# design.net
KiCad netlist of a schematic drawn in EasyEDA Pro
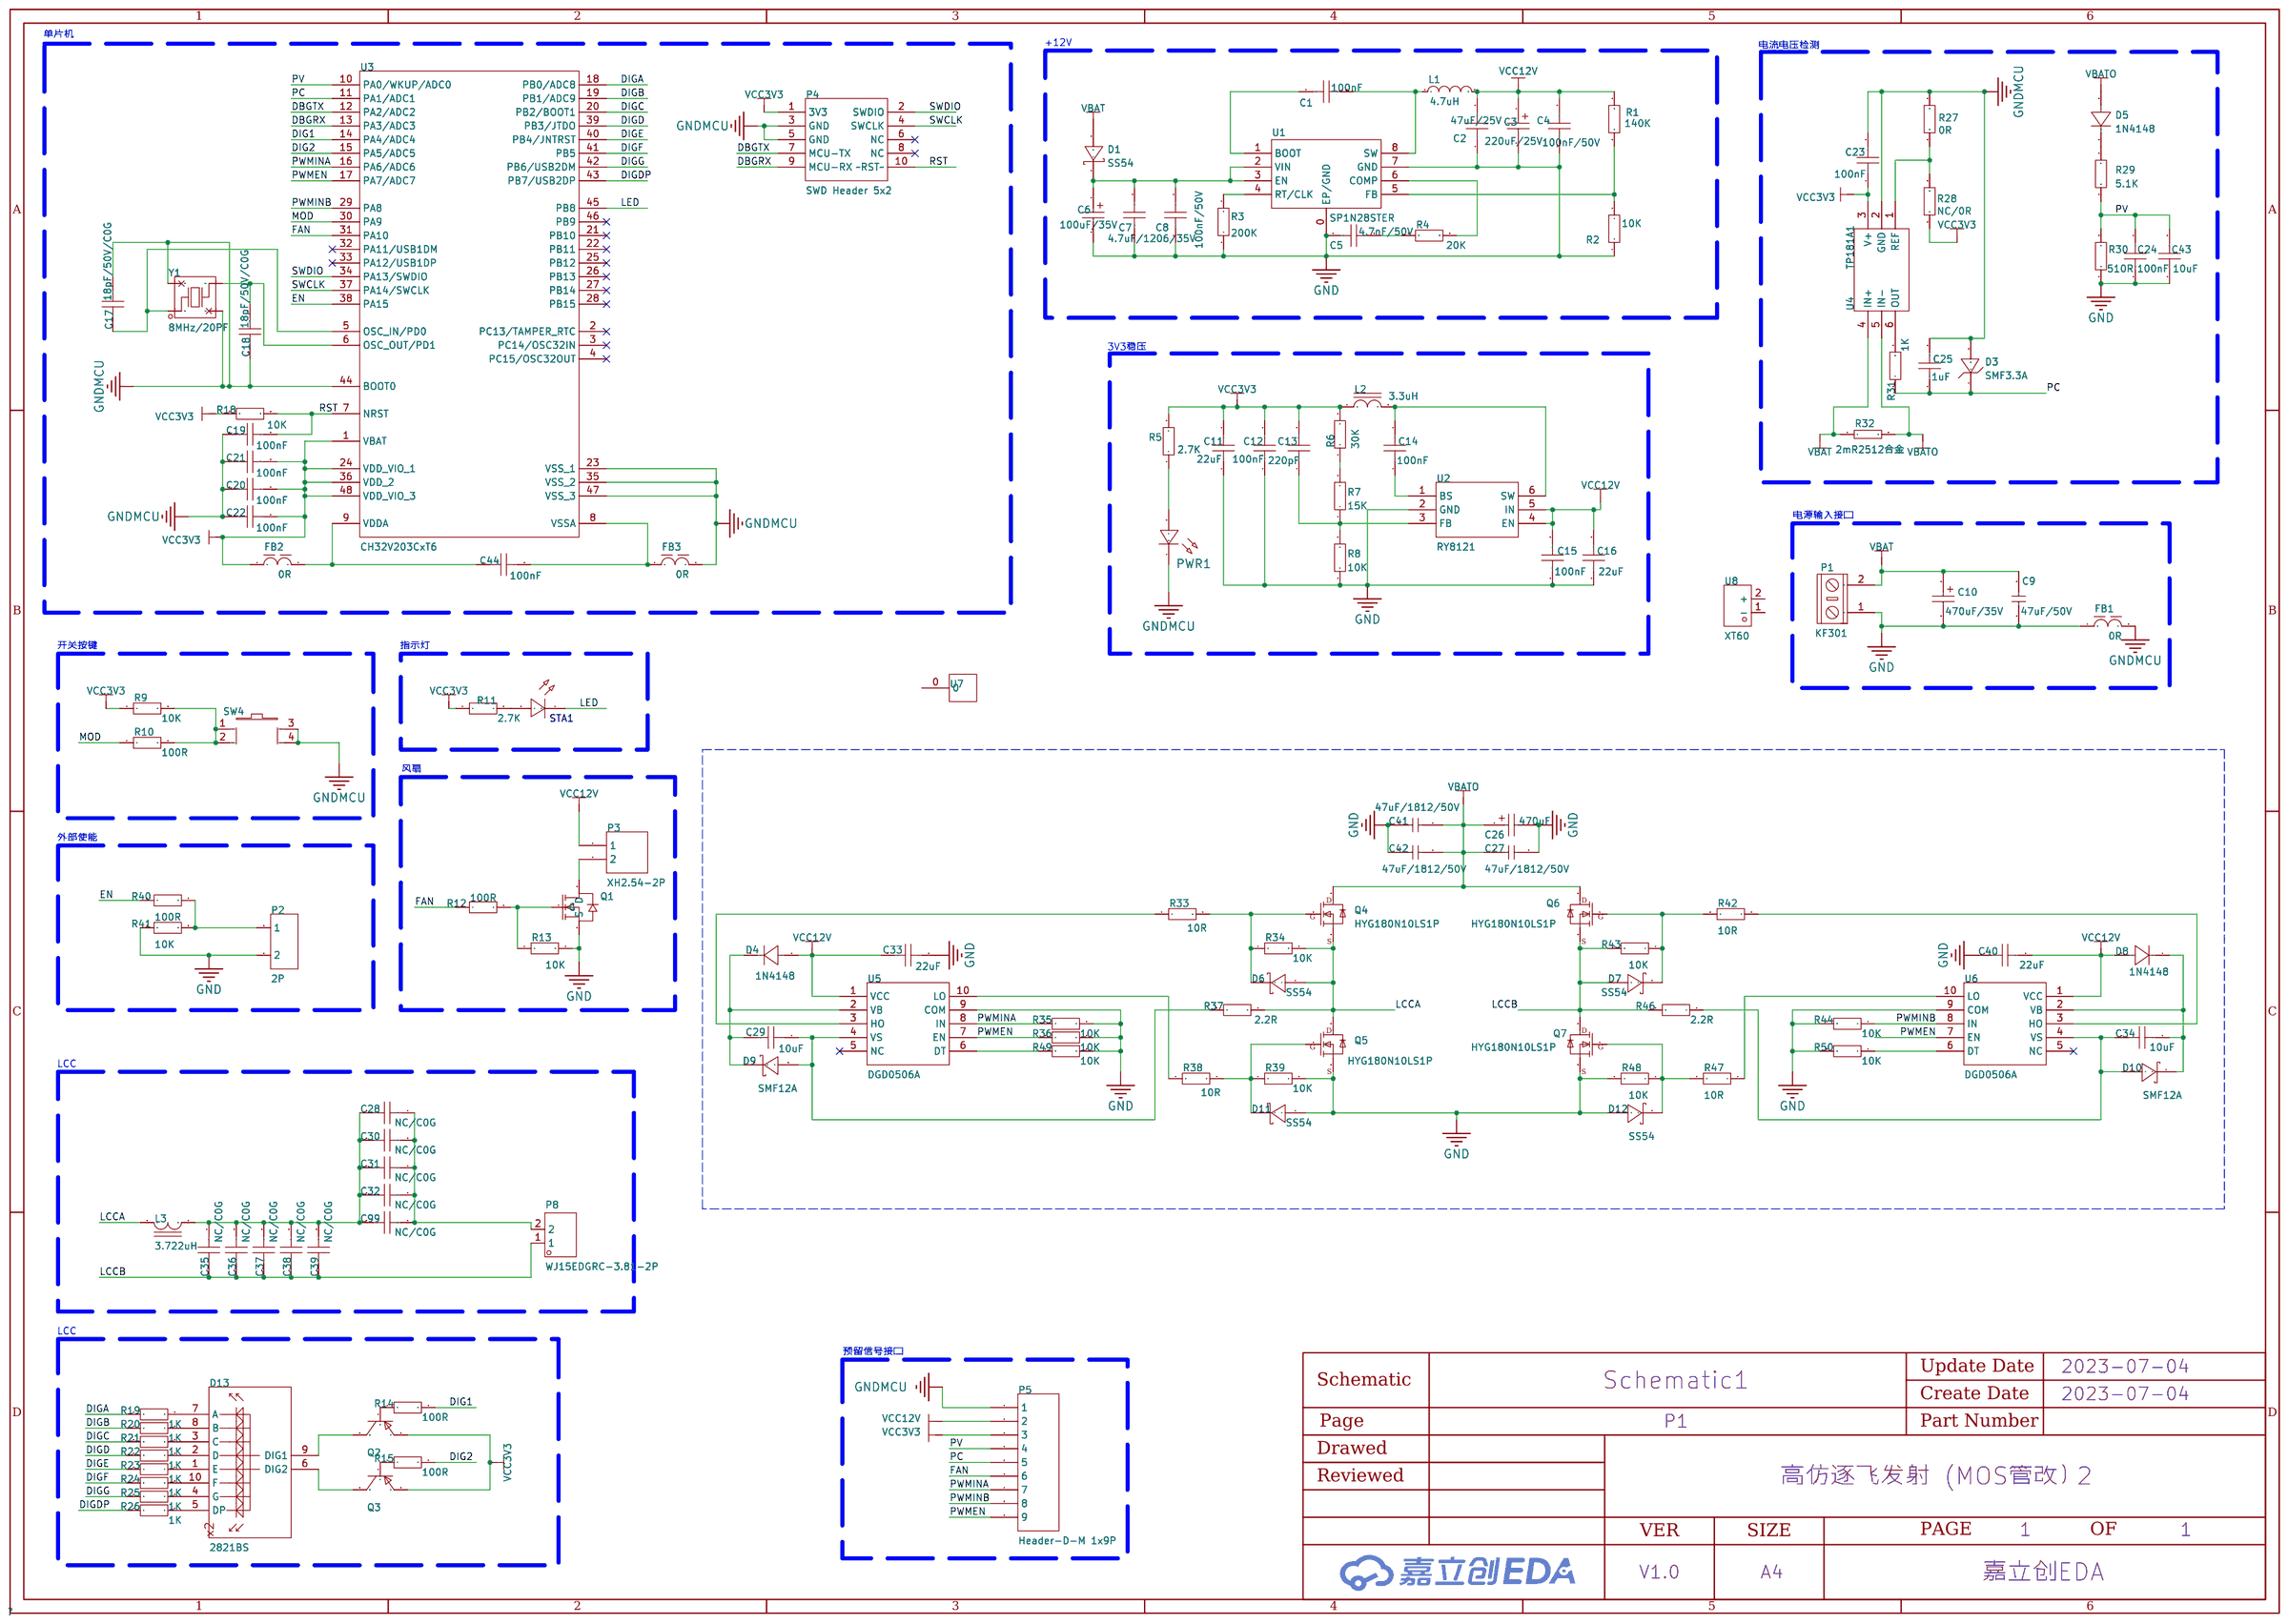
[diagram p0: schematic sheet]

(export (version "E")
  (design (tool "Eeschema 10.0.6"))
  (components
    (comp (ref "C1")
      (value "100nF")
      (footprint "easyedapro:C1206")
      (libsource (lib "easyedapro") (part "CapAcitance"))
    )
    (comp (ref "C2")
      (value "47uF/25V")
      (footprint "easyedapro:C1206")
      (libsource (lib "easyedapro") (part "CapAcitance"))
    )
    (comp (ref "C3")
      (value "220uF/25V")
      (footprint "easyedapro:Cap-S-D 2.5-6.3X8")
      (libsource (lib "easyedapro") (part "S-D 220uF 25V 6.3x8"))
    )
    (comp (ref "C4")
      (value "100nF/50V")
      (footprint "easyedapro:C1206")
      (libsource (lib "easyedapro") (part "CapAcitance"))
    )
    (comp (ref "C5")
      (value "4.7nF/50V")
      (footprint "easyedapro:C1206")
      (libsource (lib "easyedapro") (part "CapAcitance"))
    )
    (comp (ref "C6")
      (value "100uF/35V")
      (footprint "easyedapro:Cap-S-D 2.5-6.3X8")
      (libsource (lib "easyedapro") (part "S-D 100uF 35V 6.3x8"))
    )
    (comp (ref "C7")
      (value "4.7uF/1206/35V")
      (footprint "easyedapro:C1206")
      (libsource (lib "easyedapro") (part "CapAcitance"))
    )
    (comp (ref "C8")
      (value "100nF/50V")
      (footprint "easyedapro:C1206")
      (libsource (lib "easyedapro") (part "CapAcitance"))
    )
    (comp (ref "C9")
      (value "47uF/50V")
      (footprint "easyedapro:CAPC4532[1812]S")
      (libsource (lib "easyedapro") (part "47uF 1812 50V X5R"))
    )
    (comp (ref "C10")
      (value "470uF/35V")
      (footprint "easyedapro:Cap-S-D 3.5-8x14")
      (libsource (lib "easyedapro") (part "S-D 470uF 35V 8x14"))
    )
    (comp (ref "C11")
      (value "22uF")
      (footprint "easyedapro:C0805")
      (libsource (lib "easyedapro") (part "CapAcitance"))
    )
    (comp (ref "C12")
      (value "100nF")
      (footprint "easyedapro:C0805")
      (libsource (lib "easyedapro") (part "CapAcitance"))
    )
    (comp (ref "C13")
      (value "220pF")
      (footprint "easyedapro:C0805")
      (libsource (lib "easyedapro") (part "CapAcitance"))
    )
    (comp (ref "C14")
      (value "100nF")
      (footprint "easyedapro:C0805")
      (libsource (lib "easyedapro") (part "CapAcitance"))
    )
    (comp (ref "C15")
      (value "100nF")
      (footprint "easyedapro:C0805")
      (libsource (lib "easyedapro") (part "CapAcitance"))
    )
    (comp (ref "C16")
      (value "22uF")
      (footprint "easyedapro:C0805")
      (libsource (lib "easyedapro") (part "CapAcitance"))
    )
    (comp (ref "C17")
      (value "18pF/50V/C0G")
      (footprint "easyedapro:C0805")
      (libsource (lib "easyedapro") (part "CapAcitance"))
    )
    (comp (ref "C18")
      (value "18pF/50V/C0G")
      (footprint "easyedapro:C0805")
      (libsource (lib "easyedapro") (part "CapAcitance"))
    )
    (comp (ref "C19")
      (value "100nF")
      (footprint "easyedapro:C0805")
      (libsource (lib "easyedapro") (part "CapAcitance"))
    )
    (comp (ref "C20")
      (value "100nF")
      (footprint "easyedapro:C0805")
      (libsource (lib "easyedapro") (part "CapAcitance"))
    )
    (comp (ref "C21")
      (value "100nF")
      (footprint "easyedapro:C0805")
      (libsource (lib "easyedapro") (part "CapAcitance"))
    )
    (comp (ref "C22")
      (value "100nF")
      (footprint "easyedapro:C0805")
      (libsource (lib "easyedapro") (part "CapAcitance"))
    )
    (comp (ref "C23")
      (value "100nF")
      (footprint "easyedapro:C0805")
      (libsource (lib "easyedapro") (part "CapAcitance"))
    )
    (comp (ref "C24")
      (value "100nF")
      (footprint "easyedapro:C0805")
      (libsource (lib "easyedapro") (part "CapAcitance"))
    )
    (comp (ref "C25")
      (value "1uF")
      (footprint "easyedapro:C0805")
      (libsource (lib "easyedapro") (part "CapAcitance"))
    )
    (comp (ref "C26")
      (value "470uF")
      (footprint "easyedapro:Cap-S-D 3.5-8x14")
      (libsource (lib "easyedapro") (part "S-D 470uF 35V 8x14"))
    )
    (comp (ref "C27")
      (value "47uF/1812/50V")
      (footprint "easyedapro:CAPC4532[1812]S")
      (libsource (lib "easyedapro") (part "47uF 1812 50V X5R"))
    )
    (comp (ref "C28")
      (value "NC/C0G")
      (footprint "easyedapro:C0805")
      (libsource (lib "easyedapro") (part "CapAcitance"))
    )
    (comp (ref "C29")
      (value "10uF")
      (footprint "easyedapro:C0805")
      (libsource (lib "easyedapro") (part "CapAcitance"))
    )
    (comp (ref "C30")
      (value "NC/C0G")
      (footprint "easyedapro:C0805")
      (libsource (lib "easyedapro") (part "CapAcitance"))
    )
    (comp (ref "C31")
      (value "NC/C0G")
      (footprint "easyedapro:C0805")
      (libsource (lib "easyedapro") (part "CapAcitance"))
    )
    (comp (ref "C32")
      (value "NC/C0G")
      (footprint "easyedapro:C0805")
      (libsource (lib "easyedapro") (part "CapAcitance"))
    )
    (comp (ref "C33")
      (value "22uF")
      (footprint "easyedapro:C0805")
      (libsource (lib "easyedapro") (part "CapAcitance"))
    )
    (comp (ref "C34")
      (value "10uF")
      (footprint "easyedapro:C0805")
      (libsource (lib "easyedapro") (part "CapAcitance"))
    )
    (comp (ref "C35")
      (value "NC/C0G")
      (footprint "easyedapro:C0805")
      (libsource (lib "easyedapro") (part "CapAcitance"))
    )
    (comp (ref "C36")
      (value "NC/C0G")
      (footprint "easyedapro:C0805")
      (libsource (lib "easyedapro") (part "CapAcitance"))
    )
    (comp (ref "C37")
      (value "NC/C0G")
      (footprint "easyedapro:C0805")
      (libsource (lib "easyedapro") (part "CapAcitance"))
    )
    (comp (ref "C38")
      (value "NC/C0G")
      (footprint "easyedapro:C0805")
      (libsource (lib "easyedapro") (part "CapAcitance"))
    )
    (comp (ref "C39")
      (value "NC/C0G")
      (footprint "easyedapro:C0805")
      (libsource (lib "easyedapro") (part "CapAcitance"))
    )
    (comp (ref "C40")
      (value "22uF")
      (footprint "easyedapro:C0805")
      (libsource (lib "easyedapro") (part "CapAcitance"))
    )
    (comp (ref "C41")
      (value "47uF/1812/50V")
      (footprint "easyedapro:CAPC4532[1812]S")
      (libsource (lib "easyedapro") (part "47uF 1812 50V X5R"))
    )
    (comp (ref "C42")
      (value "47uF/1812/50V")
      (footprint "easyedapro:CAPC4532[1812]S")
      (libsource (lib "easyedapro") (part "47uF 1812 50V X5R"))
    )
    (comp (ref "C43")
      (value "10uF")
      (footprint "easyedapro:C0805")
      (libsource (lib "easyedapro") (part "CapAcitance"))
    )
    (comp (ref "C44")
      (value "100nF")
      (footprint "easyedapro:C0805")
      (libsource (lib "easyedapro") (part "CapAcitance"))
    )
    (comp (ref "C99")
      (value "NC/C0G")
      (footprint "easyedapro:C0805")
      (libsource (lib "easyedapro") (part "CapAcitance"))
    )
    (comp (ref "D1")
      (value "SS54")
      (footprint "easyedapro:SMA_L4.4-W2.8-LS5.4-R-RD")
      (description "直流反向耐压(Vr):40V;平均整流电流(Io):5A;正向压降(Vf):550mV@5A;")
      (fields (field (name "Manufacturer") "MDD"))
      (libsource (lib "easyedapro") (part "SS54_C22452"))
    )
    (comp (ref "D3")
      (value "SMF3.3A")
      (footprint "easyedapro:SOD-123_L2.8-W1.8-LS3.7-RD")
      (description "极性:单向;反向截止电压(Vrwm):3.3V;击穿电压:5.2V;反向漏电流(Ir):600uA;峰值脉冲电流(Ipp)@10/1000μs:25A;最大钳位电压:8V;")
      (fields (field (name "Manufacturer") "DOWO(东沃)"))
      (libsource (lib "easyedapro") (part "SMF3.3A"))
    )
    (comp (ref "D4")
      (value "1N4148")
      (footprint "easyedapro:SOD-123_L2.7-W1.6-LS3.7-RD")
      (fields (field (name "Manufacturer") "FUXINSEMI(富芯森美)"))
      (libsource (lib "easyedapro") (part "1N4148W_C908248"))
    )
    (comp (ref "D5")
      (value "1N4148")
      (footprint "easyedapro:SOD-123_L2.7-W1.6-LS3.7-RD")
      (fields (field (name "Manufacturer") "FUXINSEMI(富芯森美)"))
      (libsource (lib "easyedapro") (part "1N4148W_C908248"))
    )
    (comp (ref "D6")
      (value "SS54")
      (footprint "easyedapro:SMA_L4.4-W2.8-LS5.4-R-RD")
      (description "直流反向耐压(Vr):40V;平均整流电流(Io):5A;正向压降(Vf):550mV@5A;")
      (fields (field (name "Manufacturer") "MDD"))
      (libsource (lib "easyedapro") (part "SS54_C22452"))
    )
    (comp (ref "D7")
      (value "SS54")
      (footprint "easyedapro:SMA_L4.4-W2.8-LS5.4-R-RD")
      (description "直流反向耐压(Vr):40V;平均整流电流(Io):5A;正向压降(Vf):550mV@5A;")
      (fields (field (name "Manufacturer") "MDD"))
      (libsource (lib "easyedapro") (part "SS54_C22452"))
    )
    (comp (ref "D8")
      (value "1N4148")
      (footprint "easyedapro:SOD-123_L2.7-W1.6-LS3.7-RD")
      (fields (field (name "Manufacturer") "FUXINSEMI(富芯森美)"))
      (libsource (lib "easyedapro") (part "1N4148W_C908248"))
    )
    (comp (ref "D9")
      (value "SMF12A")
      (footprint "easyedapro:SOD-123F_L2.8-W1.8-LS3.7-RD")
      (description "极性:单向;反向截止电压(Vrwm):12V;击穿电压:13.3V;峰值脉冲电流(Ipp)@10/1000μs:-;最大钳位电压:19.9V;峰值脉冲功率(Ppp)@10/1000μs:200W;")
      (fields (field (name "Manufacturer") "Littelfuse(美国力特)"))
      (libsource (lib "easyedapro") (part "SMF12A_C207255"))
    )
    (comp (ref "D10")
      (value "SMF12A")
      (footprint "easyedapro:SOD-123F_L2.8-W1.8-LS3.7-RD")
      (description "极性:单向;反向截止电压(Vrwm):12V;击穿电压:13.3V;峰值脉冲电流(Ipp)@10/1000μs:-;最大钳位电压:19.9V;峰值脉冲功率(Ppp)@10/1000μs:200W;")
      (fields (field (name "Manufacturer") "Littelfuse(美国力特)"))
      (libsource (lib "easyedapro") (part "SMF12A_C207255"))
    )
    (comp (ref "D11")
      (value "SS54")
      (footprint "easyedapro:SMA_L4.4-W2.8-LS5.4-R-RD")
      (description "直流反向耐压(Vr):40V;平均整流电流(Io):5A;正向压降(Vf):550mV@5A;")
      (fields (field (name "Manufacturer") "MDD"))
      (libsource (lib "easyedapro") (part "SS54_C22452"))
    )
    (comp (ref "D12")
      (value "SS54")
      (footprint "easyedapro:SMA_L4.4-W2.8-LS5.4-R-RD")
      (description "直流反向耐压(Vr):40V;平均整流电流(Io):5A;正向压降(Vf):550mV@5A;")
      (fields (field (name "Manufacturer") "MDD"))
      (libsource (lib "easyedapro") (part "SS54_C22452"))
    )
    (comp (ref "D13")
      (value "2821BS")
      (footprint "easyedapro:2821AS/BS")
      (libsource (lib "easyedapro") (part "2821BS"))
    )
    (comp (ref "FB1")
      (value "0R")
      (footprint "easyedapro:INDC1608[0603]S")
      (libsource (lib "easyedapro") (part "FB-Chip"))
    )
    (comp (ref "FB2")
      (value "0R")
      (footprint "easyedapro:INDC1608[0603]S")
      (libsource (lib "easyedapro") (part "FB-Chip"))
    )
    (comp (ref "FB3")
      (value "0R")
      (footprint "easyedapro:INDC1608[0603]S")
      (libsource (lib "easyedapro") (part "FB-Chip"))
    )
    (comp (ref "L1")
      (value "4.7uH")
      (footprint "easyedapro:IND-SMD_L7.3-W6.6")
      (description "电感值:4.7uH;精度:±20%;额定电流:5.5A;饱和电流(Isat):7A;直流电阻(DCR):37mΩ;")
      (fields (field (name "Manufacturer Part") "MCS0630-4R7MPY1") (field (name "Manufacturer") "PSA(信昌电陶)"))
      (libsource (lib "easyedapro") (part "MCS0630-4R7MPY1"))
    )
    (comp (ref "L2")
      (value "3.3uH")
      (footprint "easyedapro:0402 TPC 4*4*2")
      (libsource (lib "easyedapro") (part "Ind-Power_1"))
    )
    (comp (ref "L3")
      (value "3.722uH")
      (footprint "easyedapro:T94/106-LAY")
      (libsource (lib "easyedapro") (part "Ind-Power_2"))
    )
    (comp (ref "P1")
      (value "KF301")
      (footprint "easyedapro:KF/WJ/DG 301-2p-5.0mm")
      (libsource (lib "easyedapro") (part "KF/WJ/DG 30x"))
    )
    (comp (ref "P2")
      (value "2P")
      (footprint "easyedapro:HDR-TH_2P-P2.54-V-M-1")
      (fields (field (name "Manufacturer") "TEConnectivity(美国泰科)"))
      (libsource (lib "easyedapro") (part "Header-Male-2.54_1x2"))
    )
    (comp (ref "P3")
      (value "XH2.54-2P")
      (footprint "easyedapro:XH2.54-2P-DV")
      (libsource (lib "easyedapro") (part "XH2.54-2P"))
    )
    (comp (ref "P4")
      (value "SWD Header 5x2")
      (footprint "easyedapro:HDR2X5-M")
      (libsource (lib "easyedapro") (part "SWD Header 5x2"))
    )
    (comp (ref "P5")
      (value "Header-D-M1x9P")
      (footprint "easyedapro:HDR1X9-M")
      (libsource (lib "easyedapro") (part "Header-D-M 1x9P"))
    )
    (comp (ref "P8")
      (value "WJ15EDGRC-3.81-2P")
      (footprint "easyedapro:CONN-TH_2P-P3.81_WJ15EDGRC-3.81-2P")
      (description "连接器类型:板端/插座-闭口;间距:3.81mm;排数:1;每排PIN数:2;安装方式:弯针;颜色:绿色;")
      (fields (field (name "Manufacturer") "KANGNEX(康奈克斯电气)"))
      (libsource (lib "easyedapro") (part "WJ15EDGRC-3.81-2P"))
    )
    (comp (ref "PWR1")
      (value "~")
      (footprint "easyedapro:LED_0603")
      (libsource (lib "easyedapro") (part "LED_R"))
    )
    (comp (ref "Q1")
      (value "~")
      (footprint "easyedapro:SOT-23-3_L2.9-W1.3-P1.90-LS2.4-BR")
      (libsource (lib "easyedapro") (part "N_MOS"))
    )
    (comp (ref "Q2")
      (value "~")
      (footprint "easyedapro:S8550P_SOT")
      (libsource (lib "easyedapro") (part "PNP"))
    )
    (comp (ref "Q3")
      (value "~")
      (footprint "easyedapro:S8550P_SOT")
      (libsource (lib "easyedapro") (part "PNP"))
    )
    (comp (ref "Q4")
      (value "HYG180N10LS1P")
      (footprint "easyedapro:TO-220-LAY")
      (libsource (lib "easyedapro") (part "HYG180N10LS1P"))
    )
    (comp (ref "Q5")
      (value "HYG180N10LS1P")
      (footprint "easyedapro:TO-220-LAY")
      (libsource (lib "easyedapro") (part "HYG180N10LS1P"))
    )
    (comp (ref "Q6")
      (value "HYG180N10LS1P")
      (footprint "easyedapro:TO-220-LAY")
      (libsource (lib "easyedapro") (part "HYG180N10LS1P"))
    )
    (comp (ref "Q7")
      (value "HYG180N10LS1P")
      (footprint "easyedapro:TO-220-LAY")
      (libsource (lib "easyedapro") (part "HYG180N10LS1P"))
    )
    (comp (ref "R1") (value "140K") (footprint "easyedapro:R0603") (libsource (lib "easyedapro") (part "电阻")))
    (comp (ref "R2") (value "10K") (footprint "easyedapro:R0603") (libsource (lib "easyedapro") (part "电阻")))
    (comp (ref "R3") (value "200K") (footprint "easyedapro:R0603") (libsource (lib "easyedapro") (part "电阻")))
    (comp (ref "R4") (value "20K") (footprint "easyedapro:R0603") (libsource (lib "easyedapro") (part "电阻")))
    (comp (ref "R5") (value "2.7K") (footprint "easyedapro:R0603") (libsource (lib "easyedapro") (part "电阻")))
    (comp (ref "R6") (value "30K") (footprint "easyedapro:R0603") (libsource (lib "easyedapro") (part "电阻")))
    (comp (ref "R7") (value "15K") (footprint "easyedapro:R0603") (libsource (lib "easyedapro") (part "电阻")))
    (comp (ref "R8") (value "10K") (footprint "easyedapro:R0603") (libsource (lib "easyedapro") (part "电阻")))
    (comp (ref "R9") (value "10K") (footprint "easyedapro:R0603") (libsource (lib "easyedapro") (part "电阻")))
    (comp (ref "R10")
      (value "100R")
      (footprint "easyedapro:R0603")
      (libsource (lib "easyedapro") (part "电阻"))
    )
    (comp (ref "R11")
      (value "2.7K")
      (footprint "easyedapro:R0603")
      (libsource (lib "easyedapro") (part "电阻"))
    )
    (comp (ref "R12")
      (value "100R")
      (footprint "easyedapro:R0603")
      (libsource (lib "easyedapro") (part "电阻"))
    )
    (comp (ref "R13") (value "10K") (footprint "easyedapro:R0603") (libsource (lib "easyedapro") (part "电阻")))
    (comp (ref "R14")
      (value "100R")
      (footprint "easyedapro:R0603")
      (libsource (lib "easyedapro") (part "电阻"))
    )
    (comp (ref "R15")
      (value "100R")
      (footprint "easyedapro:R0603")
      (libsource (lib "easyedapro") (part "电阻"))
    )
    (comp (ref "R18") (value "10K") (footprint "easyedapro:R0603") (libsource (lib "easyedapro") (part "电阻")))
    (comp (ref "R19") (value "1K") (footprint "easyedapro:R0603") (libsource (lib "easyedapro") (part "电阻")))
    (comp (ref "R20") (value "1K") (footprint "easyedapro:R0603") (libsource (lib "easyedapro") (part "电阻")))
    (comp (ref "R21") (value "1K") (footprint "easyedapro:R0603") (libsource (lib "easyedapro") (part "电阻")))
    (comp (ref "R22") (value "1K") (footprint "easyedapro:R0603") (libsource (lib "easyedapro") (part "电阻")))
    (comp (ref "R23") (value "1K") (footprint "easyedapro:R0603") (libsource (lib "easyedapro") (part "电阻")))
    (comp (ref "R24") (value "1K") (footprint "easyedapro:R0603") (libsource (lib "easyedapro") (part "电阻")))
    (comp (ref "R25") (value "1K") (footprint "easyedapro:R0603") (libsource (lib "easyedapro") (part "电阻")))
    (comp (ref "R26") (value "1K") (footprint "easyedapro:R0603") (libsource (lib "easyedapro") (part "电阻")))
    (comp (ref "R27") (value "0R") (footprint "easyedapro:R0603") (libsource (lib "easyedapro") (part "电阻")))
    (comp (ref "R28")
      (value "NC/0R")
      (footprint "easyedapro:R0603")
      (libsource (lib "easyedapro") (part "电阻"))
    )
    (comp (ref "R29")
      (value "5.1K")
      (footprint "easyedapro:R0603")
      (libsource (lib "easyedapro") (part "电阻"))
    )
    (comp (ref "R30")
      (value "510R")
      (footprint "easyedapro:R0603")
      (libsource (lib "easyedapro") (part "电阻"))
    )
    (comp (ref "R31") (value "1K") (footprint "easyedapro:R0603") (libsource (lib "easyedapro") (part "电阻")))
    (comp (ref "R32")
      (value "2mR2512合金")
      (footprint "easyedapro:RESC6332[2512]S")
      (libsource (lib "easyedapro") (part "Res-Chip_10"))
    )
    (comp (ref "R33") (value "10R") (footprint "easyedapro:R0603") (libsource (lib "easyedapro") (part "电阻")))
    (comp (ref "R34") (value "10K") (footprint "easyedapro:R0603") (libsource (lib "easyedapro") (part "电阻")))
    (comp (ref "R35") (value "10K") (footprint "easyedapro:R0603") (libsource (lib "easyedapro") (part "电阻")))
    (comp (ref "R36") (value "10K") (footprint "easyedapro:R0603") (libsource (lib "easyedapro") (part "电阻")))
    (comp (ref "R37")
      (value "2.2R")
      (footprint "easyedapro:R0603")
      (libsource (lib "easyedapro") (part "电阻"))
    )
    (comp (ref "R38") (value "10R") (footprint "easyedapro:R0603") (libsource (lib "easyedapro") (part "电阻")))
    (comp (ref "R39") (value "10K") (footprint "easyedapro:R0603") (libsource (lib "easyedapro") (part "电阻")))
    (comp (ref "R40")
      (value "100R")
      (footprint "easyedapro:R0603")
      (libsource (lib "easyedapro") (part "电阻"))
    )
    (comp (ref "R41") (value "10K") (footprint "easyedapro:R0603") (libsource (lib "easyedapro") (part "电阻")))
    (comp (ref "R42") (value "10R") (footprint "easyedapro:R0603") (libsource (lib "easyedapro") (part "电阻")))
    (comp (ref "R43") (value "10K") (footprint "easyedapro:R0603") (libsource (lib "easyedapro") (part "电阻")))
    (comp (ref "R44") (value "10K") (footprint "easyedapro:R0603") (libsource (lib "easyedapro") (part "电阻")))
    (comp (ref "R46")
      (value "2.2R")
      (footprint "easyedapro:R0603")
      (libsource (lib "easyedapro") (part "电阻"))
    )
    (comp (ref "R47") (value "10R") (footprint "easyedapro:R0603") (libsource (lib "easyedapro") (part "电阻")))
    (comp (ref "R48") (value "10K") (footprint "easyedapro:R0603") (libsource (lib "easyedapro") (part "电阻")))
    (comp (ref "R49") (value "10K") (footprint "easyedapro:R0603") (libsource (lib "easyedapro") (part "电阻")))
    (comp (ref "R50") (value "10K") (footprint "easyedapro:R0603") (libsource (lib "easyedapro") (part "电阻")))
    (comp (ref "STA1")
      (value "~")
      (footprint "easyedapro:LED_0603")
      (libsource (lib "easyedapro") (part "LED_B"))
    )
    (comp (ref "SW4")
      (value "PTS810SJG250SMTRLFS")
      (footprint "easyedapro:SW-SMD_4P_PTS810SJM250SMTRLFS")
      (description "触点电流:50mA;额定电压(DC):16V;电路结构:单刀单掷;安装方式:-;按钮形状:圆形按钮;带灯:-;开关长度:4.2mm;开关宽度:3.2mm;开关高度:2.5mm;")
      (fields (field (name "Manufacturer") "C&K"))
      (libsource (lib "easyedapro") (part "PTS810SJG250SMTRLFS"))
    )
    (comp (ref "U1") (value "SP1N28STER") (libsource (lib "easyedapro") (part "SP1N28STER")))
    (comp (ref "U2")
      (value "RY8121")
      (footprint "easyedapro:SOT-23-6")
      (libsource (lib "easyedapro") (part "RY8121"))
    )
    (comp (ref "U3")
      (value "CH32V203CxT6")
      (footprint "easyedapro:LQFP48_L")
      (libsource (lib "easyedapro") (part "CH32V203CxT6"))
    )
    (comp (ref "U4")
      (value "TP181A1")
      (footprint "easyedapro:SOT-363")
      (libsource (lib "easyedapro") (part "TP181Ax"))
    )
    (comp (ref "U5")
      (value "DGD0506A")
      (footprint "easyedapro:MSOP-10")
      (libsource (lib "easyedapro") (part "DGD0506A"))
    )
    (comp (ref "U6")
      (value "DGD0506A")
      (footprint "easyedapro:MSOP-10")
      (libsource (lib "easyedapro") (part "DGD0506A"))
    )
    (comp (ref "U7") (value "~") (libsource (lib "easyedapro") (part "fan")))
    (comp (ref "U8")
      (value "XT60")
      (footprint "easyedapro:CONN-TH_XT60")
      (description "模型锂电连接器 XT60-M")
      (fields (field (name "Manufacturer") "AMASS(艾迈斯)"))
      (libsource (lib "easyedapro") (part "XT60"))
    )
    (comp (ref "Y1")
      (value "8MHz/20PF")
      (footprint "easyedapro:X3225-4")
      (libsource (lib "easyedapro") (part "XTAL-4"))
    )
  )
  (nets
    (net (code "1") (name "/DBGRX") (class "Default")
      (node (ref "P4") (pin "9") (pinfunction "MCU-RX_9") (pintype "input"))
      (node (ref "U3") (pin "13") (pinfunction "PA3/ADC3_13") (pintype "input"))
    )
    (net (code "2") (name "/DBGTX") (class "Default")
      (node (ref "P4") (pin "7") (pinfunction "MCU-TX_7") (pintype "input"))
      (node (ref "U3") (pin "12") (pinfunction "PA2/ADC2_12") (pintype "input"))
    )
    (net (code "3") (name "/DIG1") (class "Default")
      (node (ref "R14") (pin "2") (pinfunction "2_2") (pintype "input"))
      (node (ref "U3") (pin "14") (pinfunction "PA4/ADC4_14") (pintype "input"))
    )
    (net (code "4") (name "/DIG2") (class "Default")
      (node (ref "R15") (pin "2") (pinfunction "2_2") (pintype "input"))
      (node (ref "U3") (pin "15") (pinfunction "PA5/ADC5_15") (pintype "input"))
    )
    (net (code "5") (name "/DIGA") (class "Default")
      (node (ref "R19") (pin "1") (pinfunction "1_1") (pintype "input"))
      (node (ref "U3") (pin "18") (pinfunction "PB0/ADC8_18") (pintype "input"))
    )
    (net (code "6") (name "/DIGB") (class "Default")
      (node (ref "R20") (pin "1") (pinfunction "1_1") (pintype "input"))
      (node (ref "U3") (pin "19") (pinfunction "PB1/ADC9_19") (pintype "input"))
    )
    (net (code "7") (name "/DIGC") (class "Default")
      (node (ref "R21") (pin "1") (pinfunction "1_1") (pintype "input"))
      (node (ref "U3") (pin "20") (pinfunction "PB2/BOOT1_20") (pintype "input"))
    )
    (net (code "8") (name "/DIGD") (class "Default")
      (node (ref "R22") (pin "1") (pinfunction "1_1") (pintype "input"))
      (node (ref "U3") (pin "39") (pinfunction "PB3/JTDO_39") (pintype "input"))
    )
    (net (code "9") (name "/DIGDP") (class "Default")
      (node (ref "R26") (pin "1") (pinfunction "1_1") (pintype "input"))
      (node (ref "U3") (pin "43") (pinfunction "PB7/USB2DP_43") (pintype "input"))
    )
    (net (code "10") (name "/DIGE") (class "Default")
      (node (ref "R23") (pin "1") (pinfunction "1_1") (pintype "input"))
      (node (ref "U3") (pin "40") (pinfunction "PB4/JNTRST_40") (pintype "input"))
    )
    (net (code "11") (name "/DIGF") (class "Default")
      (node (ref "R24") (pin "1") (pinfunction "1_1") (pintype "input"))
      (node (ref "U3") (pin "41") (pinfunction "PB5_41") (pintype "input"))
    )
    (net (code "12") (name "/DIGG") (class "Default")
      (node (ref "R25") (pin "1") (pinfunction "1_1") (pintype "input"))
      (node (ref "U3") (pin "42") (pinfunction "PB6/USB2DM_42") (pintype "input"))
    )
    (net (code "13") (name "/EN") (class "Default")
      (node (ref "R40") (pin "1") (pinfunction "1_1") (pintype "input"))
      (node (ref "U3") (pin "38") (pinfunction "PA15_38") (pintype "input"))
    )
    (net (code "14") (name "/FAN") (class "Default")
      (node (ref "P5") (pin "6") (pinfunction "6_6") (pintype "input"))
      (node (ref "R12") (pin "1") (pinfunction "1_1") (pintype "input"))
      (node (ref "U3") (pin "31") (pinfunction "PA10_31") (pintype "input"))
    )
    (net (code "15") (name "/LCCA") (class "Default")
      (node (ref "D6") (pin "1") (pinfunction "A_1") (pintype "input"))
      (node (ref "L3") (pin "2") (pinfunction "2_2") (pintype "input"))
      (node (ref "Q4") (pin "3") (pinfunction "S_3") (pintype "input"))
      (node (ref "Q5") (pin "2") (pinfunction "D_2") (pintype "input"))
      (node (ref "R34") (pin "2") (pinfunction "2_2") (pintype "input"))
      (node (ref "R37") (pin "2") (pinfunction "2_2") (pintype "input"))
    )
    (net (code "16") (name "/LCCB") (class "Default")
      (node (ref "C35") (pin "1") (pinfunction "1_1") (pintype "input"))
      (node (ref "C36") (pin "1") (pinfunction "1_1") (pintype "input"))
      (node (ref "C37") (pin "1") (pinfunction "1_1") (pintype "input"))
      (node (ref "C38") (pin "1") (pinfunction "1_1") (pintype "input"))
      (node (ref "C39") (pin "1") (pinfunction "1_1") (pintype "input"))
      (node (ref "D7") (pin "1") (pinfunction "A_1") (pintype "input"))
      (node (ref "P8") (pin "1") (pinfunction "1_1") (pintype "input"))
      (node (ref "Q6") (pin "3") (pinfunction "S_3") (pintype "input"))
      (node (ref "Q7") (pin "2") (pinfunction "D_2") (pintype "input"))
      (node (ref "R43") (pin "2") (pinfunction "2_2") (pintype "input"))
      (node (ref "R46") (pin "2") (pinfunction "2_2") (pintype "input"))
    )
    (net (code "17") (name "/LED") (class "Default")
      (node (ref "STA1") (pin "1") (pinfunction "C_1") (pintype "input"))
      (node (ref "U3") (pin "45") (pinfunction "PB8_45") (pintype "input"))
    )
    (net (code "18") (name "/MOD") (class "Default")
      (node (ref "R10") (pin "1") (pinfunction "1_1") (pintype "input"))
      (node (ref "U3") (pin "30") (pinfunction "PA9_30") (pintype "input"))
    )
    (net (code "19") (name "/PC") (class "Default")
      (node (ref "C25") (pin "1") (pinfunction "1_1") (pintype "input"))
      (node (ref "D3") (pin "1") (pinfunction "1_1") (pintype "input"))
      (node (ref "P5") (pin "5") (pinfunction "5_5") (pintype "input"))
      (node (ref "R31") (pin "1") (pinfunction "1_1") (pintype "input"))
      (node (ref "U3") (pin "11") (pinfunction "PA1/ADC1_11") (pintype "input"))
    )
    (net (code "20") (name "/PV") (class "Default")
      (node (ref "C24") (pin "2") (pinfunction "2_2") (pintype "input"))
      (node (ref "C43") (pin "2") (pinfunction "2_2") (pintype "input"))
      (node (ref "P5") (pin "4") (pinfunction "4_4") (pintype "input"))
      (node (ref "R29") (pin "1") (pinfunction "1_1") (pintype "input"))
      (node (ref "R30") (pin "2") (pinfunction "2_2") (pintype "input"))
      (node (ref "U3") (pin "10") (pinfunction "PA0/WKUP/ADC0_10") (pintype "input"))
    )
    (net (code "21") (name "/PWMEN") (class "Default")
      (node (ref "P5") (pin "9") (pinfunction "9_9") (pintype "input"))
      (node (ref "R36") (pin "1") (pinfunction "1_1") (pintype "input"))
      (node (ref "U3") (pin "17") (pinfunction "PA7/ADC7_17") (pintype "input"))
      (node (ref "U5") (pin "7") (pinfunction "EN_7") (pintype "input"))
      (node (ref "U6") (pin "7") (pinfunction "EN_7") (pintype "input"))
    )
    (net (code "22") (name "/PWMINA") (class "Default")
      (node (ref "P5") (pin "7") (pinfunction "7_7") (pintype "input"))
      (node (ref "R35") (pin "1") (pinfunction "1_1") (pintype "input"))
      (node (ref "U3") (pin "16") (pinfunction "PA6/ADC6_16") (pintype "input"))
      (node (ref "U5") (pin "8") (pinfunction "IN_8") (pintype "input"))
    )
    (net (code "23") (name "/PWMINB") (class "Default")
      (node (ref "P5") (pin "8") (pinfunction "8_8") (pintype "input"))
      (node (ref "R44") (pin "1") (pinfunction "1_1") (pintype "input"))
      (node (ref "U3") (pin "29") (pinfunction "PA8_29") (pintype "input"))
      (node (ref "U6") (pin "8") (pinfunction "IN_8") (pintype "input"))
    )
    (net (code "24") (name "/RST") (class "Default")
      (node (ref "C19") (pin "2") (pinfunction "2_2") (pintype "input"))
      (node (ref "P4") (pin "10") (pinfunction "~RST~_10") (pintype "input"))
      (node (ref "R18") (pin "2") (pinfunction "2_2") (pintype "input"))
      (node (ref "U3") (pin "7") (pinfunction "NRST_7") (pintype "input"))
    )
    (net (code "25") (name "/SWCLK") (class "Default")
      (node (ref "P4") (pin "4") (pinfunction "SWCLK_4") (pintype "input"))
      (node (ref "U3") (pin "37") (pinfunction "PA14/SWCLK_37") (pintype "input"))
    )
    (net (code "26") (name "/SWDIO") (class "Default")
      (node (ref "P4") (pin "2") (pinfunction "SWDIO_2") (pintype "input"))
      (node (ref "U3") (pin "34") (pinfunction "PA13/SWDIO_34") (pintype "input"))
    )
    (net (code "27") (name "GND") (class "Default")
      (node (ref "C10") (pin "2") (pinfunction "2_2") (pintype "input"))
      (node (ref "C11") (pin "1") (pinfunction "1_1") (pintype "input"))
      (node (ref "C12") (pin "1") (pinfunction "1_1") (pintype "input"))
      (node (ref "C15") (pin "1") (pinfunction "1_1") (pintype "input"))
      (node (ref "C16") (pin "1") (pinfunction "1_1") (pintype "input"))
      (node (ref "C2") (pin "1") (pinfunction "1_1") (pintype "input"))
      (node (ref "C24") (pin "1") (pinfunction "1_1") (pintype "input"))
      (node (ref "C26") (pin "2") (pinfunction "2_2") (pintype "input"))
      (node (ref "C27") (pin "2") (pinfunction "2_2") (pintype "input"))
      (node (ref "C3") (pin "2") (pinfunction "2_2") (pintype "input"))
      (node (ref "C33") (pin "1") (pinfunction "1_1") (pintype "input"))
      (node (ref "C4") (pin "1") (pinfunction "1_1") (pintype "input"))
      (node (ref "C40") (pin "1") (pinfunction "1_1") (pintype "input"))
      (node (ref "C41") (pin "1") (pinfunction "1_1") (pintype "input"))
      (node (ref "C42") (pin "1") (pinfunction "1_1") (pintype "input"))
      (node (ref "C43") (pin "1") (pinfunction "1_1") (pintype "input"))
      (node (ref "C5") (pin "1") (pinfunction "1_1") (pintype "input"))
      (node (ref "C6") (pin "2") (pinfunction "2_2") (pintype "input"))
      (node (ref "C7") (pin "1") (pinfunction "1_1") (pintype "input"))
      (node (ref "C8") (pin "1") (pinfunction "1_1") (pintype "input"))
      (node (ref "C9") (pin "1") (pinfunction "1_1") (pintype "input"))
      (node (ref "D11") (pin "1") (pinfunction "A_1") (pintype "input"))
      (node (ref "D12") (pin "1") (pinfunction "A_1") (pintype "input"))
      (node (ref "FB1") (pin "1") (pinfunction "1_1") (pintype "input"))
      (node (ref "P1") (pin "1") (pinfunction "1_1") (pintype "input"))
      (node (ref "P2") (pin "2") (pinfunction "2_2") (pintype "input"))
      (node (ref "Q1") (pin "2") (pinfunction "S_2") (pintype "input"))
      (node (ref "Q5") (pin "3") (pinfunction "S_3") (pintype "input"))
      (node (ref "Q7") (pin "3") (pinfunction "S_3") (pintype "input"))
      (node (ref "R13") (pin "2") (pinfunction "2_2") (pintype "input"))
      (node (ref "R2") (pin "1") (pinfunction "1_1") (pintype "input"))
      (node (ref "R3") (pin "1") (pinfunction "1_1") (pintype "input"))
      (node (ref "R30") (pin "1") (pinfunction "1_1") (pintype "input"))
      (node (ref "R35") (pin "2") (pinfunction "2_2") (pintype "input"))
      (node (ref "R36") (pin "2") (pinfunction "2_2") (pintype "input"))
      (node (ref "R39") (pin "2") (pinfunction "2_2") (pintype "input"))
      (node (ref "R41") (pin "1") (pinfunction "1_1") (pintype "input"))
      (node (ref "R44") (pin "2") (pinfunction "2_2") (pintype "input"))
      (node (ref "R48") (pin "2") (pinfunction "2_2") (pintype "input"))
      (node (ref "R49") (pin "2") (pinfunction "2_2") (pintype "input"))
      (node (ref "R50") (pin "2") (pinfunction "2_2") (pintype "input"))
      (node (ref "R8") (pin "1") (pinfunction "1_1") (pintype "input"))
      (node (ref "U1") (pin "0") (pinfunction "EP/GND_0") (pintype "input"))
      (node (ref "U1") (pin "7") (pinfunction "GND_7") (pintype "input"))
      (node (ref "U2") (pin "2") (pinfunction "GND_2") (pintype "input"))
      (node (ref "U5") (pin "9") (pinfunction "COM_9") (pintype "input"))
      (node (ref "U6") (pin "9") (pinfunction "COM_9") (pintype "input"))
    )
    (net (code "28") (name "GNDMCU") (class "Default")
      (node (ref "C17") (pin "2") (pinfunction "2_2") (pintype "input"))
      (node (ref "C18") (pin "1") (pinfunction "1_1") (pintype "input"))
      (node (ref "C19") (pin "1") (pinfunction "1_1") (pintype "input"))
      (node (ref "C20") (pin "1") (pinfunction "1_1") (pintype "input"))
      (node (ref "C21") (pin "1") (pinfunction "1_1") (pintype "input"))
      (node (ref "C22") (pin "1") (pinfunction "1_1") (pintype "input"))
      (node (ref "C23") (pin "2") (pinfunction "2_2") (pintype "input"))
      (node (ref "C25") (pin "2") (pinfunction "2_2") (pintype "input"))
      (node (ref "D3") (pin "2") (pinfunction "2_2") (pintype "input"))
      (node (ref "FB1") (pin "2") (pinfunction "2_2") (pintype "input"))
      (node (ref "FB3") (pin "2") (pinfunction "2_2") (pintype "input"))
      (node (ref "P4") (pin "3") (pinfunction "GND_3") (pintype "input"))
      (node (ref "P4") (pin "5") (pinfunction "GND_5") (pintype "input"))
      (node (ref "P5") (pin "1") (pinfunction "1_1") (pintype "input"))
      (node (ref "PWR1") (pin "1") (pinfunction "C_1") (pintype "input"))
      (node (ref "R27") (pin "2") (pinfunction "2_2") (pintype "input"))
      (node (ref "SW4") (pin "3") (pinfunction "3_3") (pintype "input"))
      (node (ref "SW4") (pin "4") (pinfunction "4_4") (pintype "input"))
      (node (ref "U3") (pin "23") (pinfunction "VSS_1_23") (pintype "input"))
      (node (ref "U3") (pin "35") (pinfunction "VSS_2_35") (pintype "input"))
      (node (ref "U3") (pin "44") (pinfunction "BOOT0_44") (pintype "input"))
      (node (ref "U3") (pin "47") (pinfunction "VSS_3_47") (pintype "input"))
      (node (ref "U4") (pin "2") (pinfunction "GND_2") (pintype "input"))
      (node (ref "Y1") (pin "2") (pinfunction "NC_2") (pintype "input"))
      (node (ref "Y1") (pin "4") (pinfunction "NC_4") (pintype "input"))
    )
    (net (code "29") (name "Net-(C5-Pad2)") (class "Default")
      (node (ref "C5") (pin "2") (pinfunction "2_2") (pintype "input"))
      (node (ref "R4") (pin "1") (pinfunction "1_1") (pintype "input"))
    )
    (net (code "30") (name "Net-(C28-Pad1)") (class "Default")
      (node (ref "C28") (pin "1") (pinfunction "1_1") (pintype "input"))
      (node (ref "C30") (pin "1") (pinfunction "1_1") (pintype "input"))
      (node (ref "C31") (pin "1") (pinfunction "1_1") (pintype "input"))
      (node (ref "C32") (pin "1") (pinfunction "1_1") (pintype "input"))
      (node (ref "C99") (pin "1") (pinfunction "1_1") (pintype "input"))
      (node (ref "P8") (pin "2") (pinfunction "2_2") (pintype "input"))
    )
    (net (code "31") (name "Net-(C28-Pad2)") (class "Default")
      (node (ref "C28") (pin "2") (pinfunction "2_2") (pintype "input"))
      (node (ref "C30") (pin "2") (pinfunction "2_2") (pintype "input"))
      (node (ref "C31") (pin "2") (pinfunction "2_2") (pintype "input"))
      (node (ref "C32") (pin "2") (pinfunction "2_2") (pintype "input"))
      (node (ref "C35") (pin "2") (pinfunction "2_2") (pintype "input"))
      (node (ref "C36") (pin "2") (pinfunction "2_2") (pintype "input"))
      (node (ref "C37") (pin "2") (pinfunction "2_2") (pintype "input"))
      (node (ref "C38") (pin "2") (pinfunction "2_2") (pintype "input"))
      (node (ref "C39") (pin "2") (pinfunction "2_2") (pintype "input"))
      (node (ref "C99") (pin "2") (pinfunction "2_2") (pintype "input"))
      (node (ref "L3") (pin "1") (pinfunction "1_1") (pintype "input"))
    )
    (net (code "32") (name "Net-(D1-K)") (class "Default")
      (node (ref "C6") (pin "1") (pinfunction "1_1") (pintype "input"))
      (node (ref "C7") (pin "2") (pinfunction "2_2") (pintype "input"))
      (node (ref "C8") (pin "2") (pinfunction "2_2") (pintype "input"))
      (node (ref "D1") (pin "2") (pinfunction "K_2") (pintype "input"))
      (node (ref "U1") (pin "2") (pinfunction "VIN_2") (pintype "input"))
      (node (ref "U1") (pin "3") (pinfunction "EN_3") (pintype "input"))
    )
    (net (code "33") (name "Net-(D4-K)") (class "Default")
      (node (ref "C29") (pin "2") (pinfunction "2_2") (pintype "input"))
      (node (ref "D4") (pin "1") (pinfunction "K_1") (pintype "input"))
      (node (ref "D9") (pin "1") (pinfunction "K_1") (pintype "input"))
      (node (ref "U5") (pin "2") (pinfunction "VB_2") (pintype "input"))
    )
    (net (code "34") (name "Net-(D5-K)") (class "Default")
      (node (ref "D5") (pin "1") (pinfunction "K_1") (pintype "input"))
      (node (ref "R29") (pin "2") (pinfunction "2_2") (pintype "input"))
    )
    (net (code "35") (name "Net-(D6-K)") (class "Default")
      (node (ref "D6") (pin "2") (pinfunction "K_2") (pintype "input"))
      (node (ref "Q4") (pin "1") (pinfunction "G_1") (pintype "input"))
      (node (ref "R33") (pin "2") (pinfunction "2_2") (pintype "input"))
      (node (ref "R34") (pin "1") (pinfunction "1_1") (pintype "input"))
    )
    (net (code "36") (name "Net-(D7-K)") (class "Default")
      (node (ref "D7") (pin "2") (pinfunction "K_2") (pintype "input"))
      (node (ref "Q6") (pin "1") (pinfunction "G_1") (pintype "input"))
      (node (ref "R42") (pin "2") (pinfunction "2_2") (pintype "input"))
      (node (ref "R43") (pin "1") (pinfunction "1_1") (pintype "input"))
    )
    (net (code "37") (name "Net-(D9-A)") (class "Default")
      (node (ref "C29") (pin "1") (pinfunction "1_1") (pintype "input"))
      (node (ref "D9") (pin "2") (pinfunction "A_2") (pintype "input"))
      (node (ref "R37") (pin "1") (pinfunction "1_1") (pintype "input"))
      (node (ref "U5") (pin "4") (pinfunction "VS_4") (pintype "input"))
    )
    (net (code "38") (name "Net-(D10-A)") (class "Default")
      (node (ref "C34") (pin "1") (pinfunction "1_1") (pintype "input"))
      (node (ref "D10") (pin "2") (pinfunction "A_2") (pintype "input"))
      (node (ref "R46") (pin "1") (pinfunction "1_1") (pintype "input"))
      (node (ref "U6") (pin "4") (pinfunction "VS_4") (pintype "input"))
    )
    (net (code "39") (name "Net-(D10-K)") (class "Default")
      (node (ref "C34") (pin "2") (pinfunction "2_2") (pintype "input"))
      (node (ref "D10") (pin "1") (pinfunction "K_1") (pintype "input"))
      (node (ref "D8") (pin "1") (pinfunction "K_1") (pintype "input"))
      (node (ref "U6") (pin "2") (pinfunction "VB_2") (pintype "input"))
    )
    (net (code "40") (name "Net-(D11-K)") (class "Default")
      (node (ref "D11") (pin "2") (pinfunction "K_2") (pintype "input"))
      (node (ref "Q5") (pin "1") (pinfunction "G_1") (pintype "input"))
      (node (ref "R38") (pin "2") (pinfunction "2_2") (pintype "input"))
      (node (ref "R39") (pin "1") (pinfunction "1_1") (pintype "input"))
    )
    (net (code "41") (name "Net-(D12-K)") (class "Default")
      (node (ref "D12") (pin "2") (pinfunction "K_2") (pintype "input"))
      (node (ref "Q7") (pin "1") (pinfunction "G_1") (pintype "input"))
      (node (ref "R47") (pin "2") (pinfunction "2_2") (pintype "input"))
      (node (ref "R48") (pin "1") (pinfunction "1_1") (pintype "input"))
    )
    (net (code "42") (name "Net-(D13-A)") (class "Default")
      (node (ref "D13") (pin "7") (pinfunction "A_7") (pintype "input"))
      (node (ref "R19") (pin "2") (pinfunction "2_2") (pintype "input"))
    )
    (net (code "43") (name "Net-(D13-B)") (class "Default")
      (node (ref "D13") (pin "8") (pinfunction "B_8") (pintype "input"))
      (node (ref "R20") (pin "2") (pinfunction "2_2") (pintype "input"))
    )
    (net (code "44") (name "Net-(D13-C)") (class "Default")
      (node (ref "D13") (pin "3") (pinfunction "C_3") (pintype "input"))
      (node (ref "R21") (pin "2") (pinfunction "2_2") (pintype "input"))
    )
    (net (code "45") (name "Net-(D13-D)") (class "Default")
      (node (ref "D13") (pin "2") (pinfunction "D_2") (pintype "input"))
      (node (ref "R22") (pin "2") (pinfunction "2_2") (pintype "input"))
    )
    (net (code "46") (name "Net-(D13-DIG1)") (class "Default")
      (node (ref "D13") (pin "9") (pinfunction "DIG1_9") (pintype "input"))
      (node (ref "Q2") (pin "3") (pinfunction "C_3") (pintype "input"))
    )
    (net (code "47") (name "Net-(D13-DIG2)") (class "Default")
      (node (ref "D13") (pin "6") (pinfunction "DIG2_6") (pintype "input"))
      (node (ref "Q3") (pin "3") (pinfunction "C_3") (pintype "input"))
    )
    (net (code "48") (name "Net-(D13-DP)") (class "Default")
      (node (ref "D13") (pin "5") (pinfunction "DP_5") (pintype "input"))
      (node (ref "R26") (pin "2") (pinfunction "2_2") (pintype "input"))
    )
    (net (code "49") (name "Net-(D13-E)") (class "Default")
      (node (ref "D13") (pin "1") (pinfunction "E_1") (pintype "input"))
      (node (ref "R23") (pin "2") (pinfunction "2_2") (pintype "input"))
    )
    (net (code "50") (name "Net-(D13-F)") (class "Default")
      (node (ref "D13") (pin "10") (pinfunction "F_10") (pintype "input"))
      (node (ref "R24") (pin "2") (pinfunction "2_2") (pintype "input"))
    )
    (net (code "51") (name "Net-(D13-G)") (class "Default")
      (node (ref "D13") (pin "4") (pinfunction "G_4") (pintype "input"))
      (node (ref "R25") (pin "2") (pinfunction "2_2") (pintype "input"))
    )
    (net (code "52") (name "Net-(P2-Pad1)") (class "Default")
      (node (ref "P2") (pin "1") (pinfunction "1_1") (pintype "input"))
      (node (ref "R40") (pin "2") (pinfunction "2_2") (pintype "input"))
      (node (ref "R41") (pin "2") (pinfunction "2_2") (pintype "input"))
    )
    (net (code "53") (name "Net-(PWR1-A)") (class "Default")
      (node (ref "PWR1") (pin "2") (pinfunction "A_2") (pintype "input"))
      (node (ref "R5") (pin "1") (pinfunction "1_1") (pintype "input"))
    )
    (net (code "54") (name "Net-(Q1-D)") (class "Default")
      (node (ref "P3") (pin "2") (pinfunction "2_2") (pintype "input"))
      (node (ref "Q1") (pin "3") (pinfunction "D_3") (pintype "input"))
    )
    (net (code "55") (name "Net-(Q1-G)") (class "Default")
      (node (ref "Q1") (pin "1") (pinfunction "G_1") (pintype "input"))
      (node (ref "R12") (pin "2") (pinfunction "2_2") (pintype "input"))
      (node (ref "R13") (pin "1") (pinfunction "1_1") (pintype "input"))
    )
    (net (code "56") (name "Net-(Q2-B)") (class "Default")
      (node (ref "Q2") (pin "1") (pinfunction "B_1") (pintype "input"))
      (node (ref "R14") (pin "1") (pinfunction "1_1") (pintype "input"))
    )
    (net (code "57") (name "Net-(Q3-B)") (class "Default")
      (node (ref "Q3") (pin "1") (pinfunction "B_1") (pintype "input"))
      (node (ref "R15") (pin "1") (pinfunction "1_1") (pintype "input"))
    )
    (net (code "58") (name "Net-(R6-Pad1)") (class "Default")
      (node (ref "R6") (pin "1") (pinfunction "1_1") (pintype "input"))
      (node (ref "R7") (pin "2") (pinfunction "2_2") (pintype "input"))
    )
    (net (code "59") (name "Net-(R10-Pad2)") (class "Default")
      (node (ref "R10") (pin "2") (pinfunction "2_2") (pintype "input"))
      (node (ref "R9") (pin "2") (pinfunction "2_2") (pintype "input"))
      (node (ref "SW4") (pin "1") (pinfunction "1_1") (pintype "input"))
      (node (ref "SW4") (pin "2") (pinfunction "2_2") (pintype "input"))
    )
    (net (code "60") (name "Net-(STA1-A)") (class "Default")
      (node (ref "R11") (pin "2") (pinfunction "2_2") (pintype "input"))
      (node (ref "STA1") (pin "2") (pinfunction "A_2") (pintype "input"))
    )
    (net (code "61") (name "Net-(U1-BOOT)") (class "Default")
      (node (ref "C1") (pin "1") (pinfunction "1_1") (pintype "input"))
      (node (ref "U1") (pin "1") (pinfunction "BOOT_1") (pintype "input"))
    )
    (net (code "62") (name "Net-(U1-COMP)") (class "Default")
      (node (ref "R4") (pin "2") (pinfunction "2_2") (pintype "input"))
      (node (ref "U1") (pin "6") (pinfunction "COMP_6") (pintype "input"))
    )
    (net (code "63") (name "Net-(U1-FB)") (class "Default")
      (node (ref "R1") (pin "1") (pinfunction "1_1") (pintype "input"))
      (node (ref "R2") (pin "2") (pinfunction "2_2") (pintype "input"))
      (node (ref "U1") (pin "5") (pinfunction "FB_5") (pintype "input"))
    )
    (net (code "64") (name "Net-(U1-RT{slash}CLK)") (class "Default")
      (node (ref "R3") (pin "2") (pinfunction "2_2") (pintype "input"))
      (node (ref "U1") (pin "4") (pinfunction "RT/CLK_4") (pintype "input"))
    )
    (net (code "65") (name "Net-(U1-SW)") (class "Default")
      (node (ref "C1") (pin "2") (pinfunction "2_2") (pintype "input"))
      (node (ref "L1") (pin "1") (pinfunction "1_1") (pintype "input"))
      (node (ref "U1") (pin "8") (pinfunction "SW_8") (pintype "input"))
    )
    (net (code "66") (name "Net-(U2-BS)") (class "Default")
      (node (ref "C14") (pin "1") (pinfunction "1_1") (pintype "input"))
      (node (ref "U2") (pin "1") (pinfunction "BS_1") (pintype "input"))
    )
    (net (code "67") (name "Net-(U2-FB)") (class "Default")
      (node (ref "C13") (pin "1") (pinfunction "1_1") (pintype "input"))
      (node (ref "R7") (pin "1") (pinfunction "1_1") (pintype "input"))
      (node (ref "R8") (pin "2") (pinfunction "2_2") (pintype "input"))
      (node (ref "U2") (pin "3") (pinfunction "FB_3") (pintype "input"))
    )
    (net (code "68") (name "Net-(U2-SW)") (class "Default")
      (node (ref "C14") (pin "2") (pinfunction "2_2") (pintype "input"))
      (node (ref "L2") (pin "2") (pinfunction "2_2") (pintype "input"))
      (node (ref "U2") (pin "6") (pinfunction "SW_6") (pintype "input"))
    )
    (net (code "69") (name "Net-(U3-OSC_IN{slash}PD0)") (class "Default")
      (node (ref "C17") (pin "1") (pinfunction "1_1") (pintype "input"))
      (node (ref "U3") (pin "5") (pinfunction "OSC_IN/PD0_5") (pintype "input"))
      (node (ref "Y1") (pin "1") (pinfunction "OSC1_1") (pintype "input"))
    )
    (net (code "70") (name "Net-(U3-OSC_OUT{slash}PD1)") (class "Default")
      (node (ref "C18") (pin "2") (pinfunction "2_2") (pintype "input"))
      (node (ref "U3") (pin "6") (pinfunction "OSC_OUT/PD1_6") (pintype "input"))
      (node (ref "Y1") (pin "3") (pinfunction "OSC2_3") (pintype "input"))
    )
    (net (code "71") (name "Net-(U3-VDDA)") (class "Default")
      (node (ref "C44") (pin "1") (pinfunction "1_1") (pintype "input"))
      (node (ref "FB2") (pin "2") (pinfunction "2_2") (pintype "input"))
      (node (ref "U3") (pin "9") (pinfunction "VDDA_9") (pintype "input"))
    )
    (net (code "72") (name "Net-(U3-VSSA)") (class "Default")
      (node (ref "C44") (pin "2") (pinfunction "2_2") (pintype "input"))
      (node (ref "FB3") (pin "1") (pinfunction "1_1") (pintype "input"))
      (node (ref "U3") (pin "8") (pinfunction "VSSA_8") (pintype "input"))
    )
    (net (code "73") (name "Net-(U4-OUT)") (class "Default")
      (node (ref "R31") (pin "2") (pinfunction "2_2") (pintype "input"))
      (node (ref "U4") (pin "6") (pinfunction "OUT_6") (pintype "input"))
    )
    (net (code "74") (name "Net-(U4-REF)") (class "Default")
      (node (ref "R27") (pin "1") (pinfunction "1_1") (pintype "input"))
      (node (ref "R28") (pin "2") (pinfunction "2_2") (pintype "input"))
      (node (ref "U4") (pin "1") (pinfunction "REF_1") (pintype "input"))
    )
    (net (code "75") (name "Net-(U5-DT)") (class "Default")
      (node (ref "R49") (pin "1") (pinfunction "1_1") (pintype "input"))
      (node (ref "U5") (pin "6") (pinfunction "DT_6") (pintype "input"))
    )
    (net (code "76") (name "Net-(U5-HO)") (class "Default")
      (node (ref "R33") (pin "1") (pinfunction "1_1") (pintype "input"))
      (node (ref "U5") (pin "3") (pinfunction "HO_3") (pintype "input"))
    )
    (net (code "77") (name "Net-(U5-LO)") (class "Default")
      (node (ref "R38") (pin "1") (pinfunction "1_1") (pintype "input"))
      (node (ref "U5") (pin "10") (pinfunction "LO_10") (pintype "input"))
    )
    (net (code "78") (name "Net-(U6-DT)") (class "Default")
      (node (ref "R50") (pin "1") (pinfunction "1_1") (pintype "input"))
      (node (ref "U6") (pin "6") (pinfunction "DT_6") (pintype "input"))
    )
    (net (code "79") (name "Net-(U6-HO)") (class "Default")
      (node (ref "R42") (pin "1") (pinfunction "1_1") (pintype "input"))
      (node (ref "U6") (pin "3") (pinfunction "HO_3") (pintype "input"))
    )
    (net (code "80") (name "Net-(U6-LO)") (class "Default")
      (node (ref "R47") (pin "1") (pinfunction "1_1") (pintype "input"))
      (node (ref "U6") (pin "10") (pinfunction "LO_10") (pintype "input"))
    )
    (net (code "81") (name "VBAT") (class "Default")
      (node (ref "C10") (pin "1") (pinfunction "1_1") (pintype "input"))
      (node (ref "C9") (pin "2") (pinfunction "2_2") (pintype "input"))
      (node (ref "D1") (pin "1") (pinfunction "A_1") (pintype "input"))
      (node (ref "P1") (pin "2") (pinfunction "2_2") (pintype "input"))
      (node (ref "R32") (pin "1") (pinfunction "1_1") (pintype "input"))
      (node (ref "U4") (pin "4") (pinfunction "IN+_4") (pintype "input"))
    )
    (net (code "82") (name "VBATO") (class "Default")
      (node (ref "C26") (pin "1") (pinfunction "1_1") (pintype "input"))
      (node (ref "C27") (pin "1") (pinfunction "1_1") (pintype "input"))
      (node (ref "C41") (pin "2") (pinfunction "2_2") (pintype "input"))
      (node (ref "C42") (pin "2") (pinfunction "2_2") (pintype "input"))
      (node (ref "D5") (pin "2") (pinfunction "A_2") (pintype "input"))
      (node (ref "Q4") (pin "2") (pinfunction "D_2") (pintype "input"))
      (node (ref "Q6") (pin "2") (pinfunction "D_2") (pintype "input"))
      (node (ref "R32") (pin "2") (pinfunction "2_2") (pintype "input"))
      (node (ref "U4") (pin "5") (pinfunction "IN-_5") (pintype "input"))
    )
    (net (code "83") (name "VCC3V3") (class "Default")
      (node (ref "C11") (pin "2") (pinfunction "2_2") (pintype "input"))
      (node (ref "C12") (pin "2") (pinfunction "2_2") (pintype "input"))
      (node (ref "C13") (pin "2") (pinfunction "2_2") (pintype "input"))
      (node (ref "C20") (pin "2") (pinfunction "2_2") (pintype "input"))
      (node (ref "C21") (pin "2") (pinfunction "2_2") (pintype "input"))
      (node (ref "C22") (pin "2") (pinfunction "2_2") (pintype "input"))
      (node (ref "C23") (pin "1") (pinfunction "1_1") (pintype "input"))
      (node (ref "FB2") (pin "1") (pinfunction "1_1") (pintype "input"))
      (node (ref "L2") (pin "1") (pinfunction "1_1") (pintype "input"))
      (node (ref "P4") (pin "1") (pinfunction "3V3_1") (pintype "input"))
      (node (ref "P5") (pin "3") (pinfunction "3_3") (pintype "input"))
      (node (ref "Q2") (pin "2") (pinfunction "E_2") (pintype "input"))
      (node (ref "Q3") (pin "2") (pinfunction "E_2") (pintype "input"))
      (node (ref "R11") (pin "1") (pinfunction "1_1") (pintype "input"))
      (node (ref "R18") (pin "1") (pinfunction "1_1") (pintype "input"))
      (node (ref "R28") (pin "1") (pinfunction "1_1") (pintype "input"))
      (node (ref "R5") (pin "2") (pinfunction "2_2") (pintype "input"))
      (node (ref "R6") (pin "2") (pinfunction "2_2") (pintype "input"))
      (node (ref "R9") (pin "1") (pinfunction "1_1") (pintype "input"))
      (node (ref "U3") (pin "1") (pinfunction "VBAT_1") (pintype "input"))
      (node (ref "U3") (pin "24") (pinfunction "VDD_VIO_1_24") (pintype "input"))
      (node (ref "U3") (pin "36") (pinfunction "VDD_2_36") (pintype "input"))
      (node (ref "U3") (pin "48") (pinfunction "VDD_VIO_3_48") (pintype "input"))
      (node (ref "U4") (pin "3") (pinfunction "V+_3") (pintype "input"))
    )
    (net (code "84") (name "VCC12V") (class "Default")
      (node (ref "C15") (pin "2") (pinfunction "2_2") (pintype "input"))
      (node (ref "C16") (pin "2") (pinfunction "2_2") (pintype "input"))
      (node (ref "C2") (pin "2") (pinfunction "2_2") (pintype "input"))
      (node (ref "C3") (pin "1") (pinfunction "1_1") (pintype "input"))
      (node (ref "C33") (pin "2") (pinfunction "2_2") (pintype "input"))
      (node (ref "C4") (pin "2") (pinfunction "2_2") (pintype "input"))
      (node (ref "C40") (pin "2") (pinfunction "2_2") (pintype "input"))
      (node (ref "D4") (pin "2") (pinfunction "A_2") (pintype "input"))
      (node (ref "D8") (pin "2") (pinfunction "A_2") (pintype "input"))
      (node (ref "L1") (pin "2") (pinfunction "2_2") (pintype "input"))
      (node (ref "P3") (pin "1") (pinfunction "1_1") (pintype "input"))
      (node (ref "P5") (pin "2") (pinfunction "2_2") (pintype "input"))
      (node (ref "R1") (pin "2") (pinfunction "2_2") (pintype "input"))
      (node (ref "U2") (pin "4") (pinfunction "EN_4") (pintype "input"))
      (node (ref "U2") (pin "5") (pinfunction "IN_5") (pintype "input"))
      (node (ref "U5") (pin "1") (pinfunction "VCC_1") (pintype "input"))
      (node (ref "U6") (pin "1") (pinfunction "VCC_1") (pintype "input"))
    )
    (net (code "85") (name "unconnected-(P4-NC-Pad6)") (class "Default")
      (node (ref "P4") (pin "6") (pinfunction "NC_6") (pintype "input+no_connect"))
    )
    (net (code "86") (name "unconnected-(P4-NC-Pad8)") (class "Default")
      (node (ref "P4") (pin "8") (pinfunction "NC_8") (pintype "input+no_connect"))
    )
    (net (code "87") (name "unconnected-(U3-PA11{slash}USB1DM-Pad32)") (class "Default")
      (node (ref "U3") (pin "32") (pinfunction "PA11/USB1DM_32") (pintype "input+no_connect"))
    )
    (net (code "88") (name "unconnected-(U3-PA12{slash}USB1DP-Pad33)") (class "Default")
      (node (ref "U3") (pin "33") (pinfunction "PA12/USB1DP_33") (pintype "input+no_connect"))
    )
    (net (code "89") (name "unconnected-(U3-PB9-Pad46)") (class "Default")
      (node (ref "U3") (pin "46") (pinfunction "PB9_46") (pintype "input+no_connect"))
    )
    (net (code "90") (name "unconnected-(U3-PB10-Pad21)") (class "Default")
      (node (ref "U3") (pin "21") (pinfunction "PB10_21") (pintype "input+no_connect"))
    )
    (net (code "91") (name "unconnected-(U3-PB11-Pad22)") (class "Default")
      (node (ref "U3") (pin "22") (pinfunction "PB11_22") (pintype "input+no_connect"))
    )
    (net (code "92") (name "unconnected-(U3-PB12-Pad25)") (class "Default")
      (node (ref "U3") (pin "25") (pinfunction "PB12_25") (pintype "input+no_connect"))
    )
    (net (code "93") (name "unconnected-(U3-PB13-Pad26)") (class "Default")
      (node (ref "U3") (pin "26") (pinfunction "PB13_26") (pintype "input+no_connect"))
    )
    (net (code "94") (name "unconnected-(U3-PB14-Pad27)") (class "Default")
      (node (ref "U3") (pin "27") (pinfunction "PB14_27") (pintype "input+no_connect"))
    )
    (net (code "95") (name "unconnected-(U3-PB15-Pad28)") (class "Default")
      (node (ref "U3") (pin "28") (pinfunction "PB15_28") (pintype "input+no_connect"))
    )
    (net (code "96") (name "unconnected-(U3-PC13{slash}TAMPER_RTC-Pad2)") (class "Default")
      (node (ref "U3") (pin "2") (pinfunction "PC13/TAMPER_RTC_2") (pintype "input+no_connect"))
    )
    (net (code "97") (name "unconnected-(U3-PC14{slash}OSC32IN-Pad3)") (class "Default")
      (node (ref "U3") (pin "3") (pinfunction "PC14/OSC32IN_3") (pintype "input+no_connect"))
    )
    (net (code "98") (name "unconnected-(U3-PC15{slash}OSC32OUT-Pad4)") (class "Default")
      (node (ref "U3") (pin "4") (pinfunction "PC15/OSC32OUT_4") (pintype "input+no_connect"))
    )
    (net (code "99") (name "unconnected-(U5-NC-Pad5)") (class "Default")
      (node (ref "U5") (pin "5") (pinfunction "NC_5") (pintype "input+no_connect"))
    )
    (net (code "100") (name "unconnected-(U6-NC-Pad5)") (class "Default")
      (node (ref "U6") (pin "5") (pinfunction "NC_5") (pintype "input+no_connect"))
    )
    (net (code "101") (name "unconnected-(U7-Pad0)") (class "Default")
      (node (ref "U7") (pin "0") (pinfunction "0_0") (pintype "input"))
    )
    (net (code "102") (name "unconnected-(U8-+-Pad2)") (class "Default")
      (node (ref "U8") (pin "2") (pinfunction "+_2") (pintype "input"))
    )
    (net (code "103") (name "unconnected-(U8---Pad1)") (class "Default")
      (node (ref "U8") (pin "1") (pinfunction "-_1") (pintype "input"))
    )
  )
)
